# PPG_AFE_first_revision.net
KiCad netlist of a schematic drawn in EAGLE
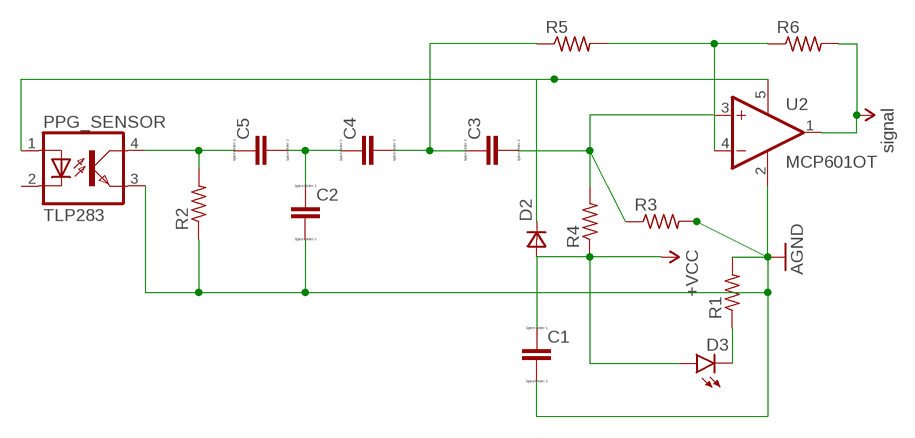
[diagram p0: schematic, sheet 1]

(export (version "E")
  (design (tool "Eeschema 10.0.6"))
  (components
    (comp (ref "C1")
      (value "CC0201")
      (footprint "eagle-import:C0201")
      (libsource (lib "eagle-import") (part "CC0201"))
    )
    (comp (ref "C2")
      (value "CC0201")
      (footprint "eagle-import:C0201")
      (libsource (lib "eagle-import") (part "CC0201"))
    )
    (comp (ref "C3")
      (value "CC0201")
      (footprint "eagle-import:C0201")
      (libsource (lib "eagle-import") (part "CC0201"))
    )
    (comp (ref "C4")
      (value "CC0201")
      (footprint "eagle-import:C0201")
      (libsource (lib "eagle-import") (part "CC0201"))
    )
    (comp (ref "C5")
      (value "CC0201")
      (footprint "eagle-import:C0201")
      (libsource (lib "eagle-import") (part "CC0201"))
    )
    (comp (ref "D2")
      (value "DSOD323")
      (footprint "eagle-import:SOD323")
      (fields (field (name "MPN") "CDSOD323-T05C"))
      (libsource (lib "eagle-import") (part "DSOD323"))
    )
    (comp (ref "D3")
      (value "LED-FKIT-1206")
      (footprint "eagle-import:FKIT-LED-1206")
      (libsource (lib "eagle-import") (part "LED-FKIT-1206"))
    )
    (comp (ref "PPG_SENSOR")
      (value "TLP283")
      (footprint "eagle-import:MINI-FLAT-4")
      (libsource (lib "eagle-import") (part "TLP283"))
    )
    (comp (ref "R1")
      (value "R-US_R0603")
      (footprint "eagle-import:R0603")
      (libsource (lib "eagle-import") (part "R-US_R0603"))
    )
    (comp (ref "R2")
      (value "R-US_R0603")
      (footprint "eagle-import:R0603")
      (libsource (lib "eagle-import") (part "R-US_R0603"))
    )
    (comp (ref "R3")
      (value "R-US_R0603")
      (footprint "eagle-import:R0603")
      (libsource (lib "eagle-import") (part "R-US_R0603"))
    )
    (comp (ref "R4")
      (value "R-US_R0603")
      (footprint "eagle-import:R0603")
      (libsource (lib "eagle-import") (part "R-US_R0603"))
    )
    (comp (ref "R5")
      (value "R-US_R0603")
      (footprint "eagle-import:R0603")
      (libsource (lib "eagle-import") (part "R-US_R0603"))
    )
    (comp (ref "R6")
      (value "R-US_R0603")
      (footprint "eagle-import:R0603")
      (libsource (lib "eagle-import") (part "R-US_R0603"))
    )
    (comp (ref "U2")
      (value "MCP601OT")
      (footprint "eagle-import:SOT23-5")
      (libsource (lib "eagle-import") (part "MCP601OT"))
    )
  )
  (nets
    (net (code "1") (name "+VCC") (class "Default")
      (node (ref "C1") (pin "1") (pinfunction "1_1") (pintype "passive"))
      (node (ref "D2") (pin "2") (pinfunction "A_2") (pintype "passive"))
      (node (ref "D3") (pin "A") (pinfunction "A_A") (pintype "passive"))
      (node (ref "R4") (pin "1") (pinfunction "1_1") (pintype "passive"))
    )
    (net (code "2") (name "AGND") (class "Default")
      (node (ref "C1") (pin "2") (pinfunction "2_2") (pintype "passive"))
      (node (ref "C2") (pin "2") (pinfunction "2_2") (pintype "passive"))
      (node (ref "PPG_SENSOR") (pin "3") (pinfunction "EMIT_3") (pintype "passive"))
      (node (ref "R1") (pin "2") (pinfunction "2_2") (pintype "passive"))
      (node (ref "R2") (pin "1") (pinfunction "1_1") (pintype "passive"))
      (node (ref "R3") (pin "2") (pinfunction "2_2") (pintype "passive"))
      (node (ref "U2") (pin "2") (pinfunction "V-_2") (pintype "power_in"))
    )
    (net (code "3") (name "Net-(C2-Pad1)") (class "Default")
      (node (ref "C2") (pin "1") (pinfunction "1_1") (pintype "passive"))
      (node (ref "C4") (pin "1") (pinfunction "1_1") (pintype "passive"))
      (node (ref "C5") (pin "2") (pinfunction "2_2") (pintype "passive"))
    )
    (net (code "4") (name "Net-(C3-Pad1)") (class "Default")
      (node (ref "C3") (pin "1") (pinfunction "1_1") (pintype "passive"))
      (node (ref "C4") (pin "2") (pinfunction "2_2") (pintype "passive"))
      (node (ref "R5") (pin "1") (pinfunction "1_1") (pintype "passive"))
    )
    (net (code "5") (name "Net-(D2-C)") (class "Default")
      (node (ref "D2") (pin "1") (pinfunction "C_1") (pintype "passive"))
      (node (ref "PPG_SENSOR") (pin "1") (pinfunction "A_1") (pintype "passive"))
      (node (ref "U2") (pin "5") (pinfunction "V+_5") (pintype "power_in"))
    )
    (net (code "6") (name "Net-(D3-PadC)") (class "Default")
      (node (ref "D3") (pin "C") (pinfunction "C_C") (pintype "passive"))
      (node (ref "R1") (pin "1") (pinfunction "1_1") (pintype "passive"))
    )
    (net (code "7") (name "Net-(PPG_SENSOR-COL)") (class "Default")
      (node (ref "C5") (pin "1") (pinfunction "1_1") (pintype "passive"))
      (node (ref "PPG_SENSOR") (pin "4") (pinfunction "COL_4") (pintype "passive"))
      (node (ref "R2") (pin "2") (pinfunction "2_2") (pintype "passive"))
    )
    (net (code "8") (name "Net-(U2-+IN)") (class "Default")
      (node (ref "C3") (pin "2") (pinfunction "2_2") (pintype "passive"))
      (node (ref "R3") (pin "1") (pinfunction "1_1") (pintype "passive"))
      (node (ref "R4") (pin "2") (pinfunction "2_2") (pintype "passive"))
      (node (ref "U2") (pin "3") (pinfunction "+IN_3") (pintype "input"))
    )
    (net (code "9") (name "Net-(U2--IN)") (class "Default")
      (node (ref "R5") (pin "2") (pinfunction "2_2") (pintype "passive"))
      (node (ref "R6") (pin "1") (pinfunction "1_1") (pintype "passive"))
      (node (ref "U2") (pin "4") (pinfunction "-IN_4") (pintype "input"))
    )
    (net (code "10") (name "signal") (class "Default")
      (node (ref "R6") (pin "2") (pinfunction "2_2") (pintype "passive"))
      (node (ref "U2") (pin "1") (pinfunction "OUT_1") (pintype "output"))
    )
    (net (code "11") (name "unconnected-(PPG_SENSOR-C-Pad2)") (class "Default")
      (node (ref "PPG_SENSOR") (pin "2") (pinfunction "C_2") (pintype "passive"))
    )
  )
)
